# Main.net
KiCad netlist of a schematic drawn in Altium Designer
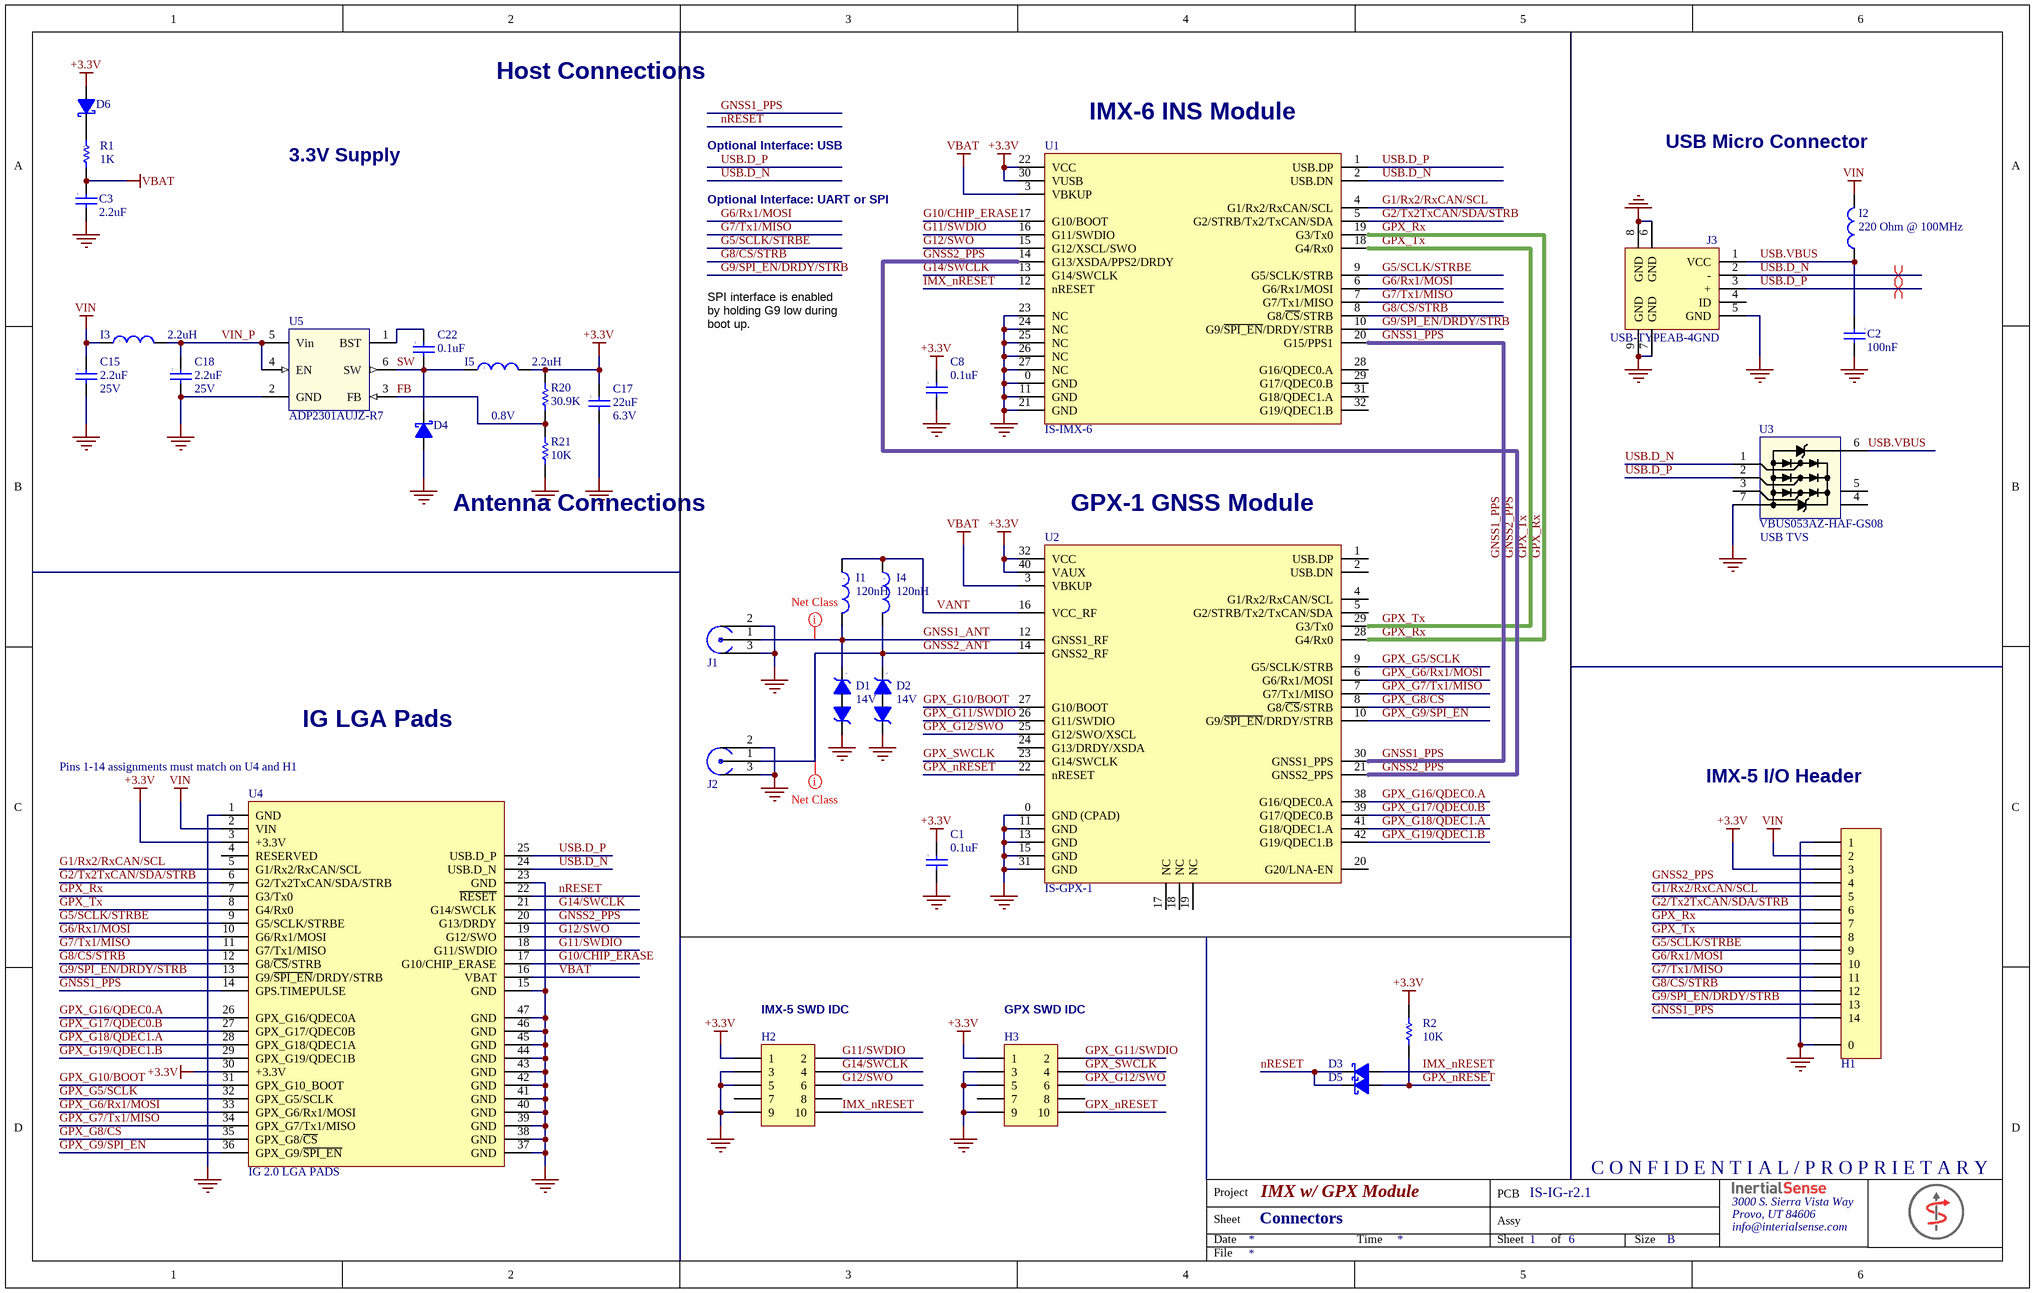
[diagram p0: Main.SchDoc]

(export (version "E")
  (design (tool "Eeschema 10.0.6"))
  (components
    (comp (ref "C1")
      (value "0.1uF")
      (footprint "0402")
      (description "CAP CER .10UF 50V X7R 10% 0402")
      (fields
        (field (name "MANUFACTURER") "TDK Corporation")
        (field (name "MANUFACTURER PART NUMBER") "C1005X7R1H104K")
        (field (name "PUBLISHER") "Altium Limited")
      )
      (libsource (lib "General") (part "Cap"))
    )
    (comp (ref "C2")
      (value "100nF")
      (footprint "0402")
      (description "CAP CER .10UF 50V X7R 10% 0402")
      (fields
        (field (name "MANUFACTURER") "TDK Corporation")
        (field (name "MANUFACTURER PART NUMBER") "C1005X7R1H104K")
        (field (name "PUBLISHER") "Altium Limited")
      )
      (libsource (lib "General") (part "Cap"))
    )
    (comp (ref "C3")
      (value "2.2uF")
      (footprint "0402")
      (description "0402 2.2 uF 6.3 V ±10% Tolerance X6S Multilayer Ceramic Capacitor")
      (fields
        (field (name "MANUFACTURER") "Murata")
        (field (name "MANUFACTURER PART NUMBER") "GRM155C80J225KE95D")
        (field (name "PUBLISHER") "Altium Limited")
      )
      (libsource (lib "General") (part "Cap"))
    )
    (comp (ref "C8")
      (value "0.1uF")
      (footprint "0402")
      (description "CAP CER .10UF 50V X7R 10% 0402")
      (fields
        (field (name "MANUFACTURER") "TDK Corporation")
        (field (name "MANUFACTURER PART NUMBER") "C1005X7R1H104K")
        (field (name "PUBLISHER") "Altium Limited")
      )
      (libsource (lib "General") (part "Cap"))
    )
    (comp (ref "C15")
      (value "2.2uF")
      (footprint "0603")
      (description "CAP CER 2.2UF 25V X6S 0603")
      (fields
        (field (name "MANUFACTURER") "Murata")
        (field (name "MANUFACTURER PART NUMBER") "GRT188C81E225KE13D")
        (field (name "VOLTAGE RATING") "25V")
        (field (name "PUBLISHER") "Altium Limited")
      )
      (libsource (lib "General") (part "Cap"))
    )
    (comp (ref "C17")
      (value "22uF")
      (footprint "0603")
      (description "CAP CER 22UF 6.3V X6S 0603")
      (fields
        (field (name "MANUFACTURER") "Murata")
        (field (name "MANUFACTURER PART NUMBER") "GRM188C80J226ME15D")
        (field (name "VOLTAGE RATING") "6.3V")
        (field (name "PUBLISHER") "Altium Limited")
      )
      (libsource (lib "General") (part "Cap"))
    )
    (comp (ref "C18")
      (value "2.2uF")
      (footprint "0603")
      (description "CAP CER 2.2UF 25V X6S 0603")
      (fields
        (field (name "MANUFACTURER") "Murata")
        (field (name "MANUFACTURER PART NUMBER") "GRT188C81E225KE13D")
        (field (name "VOLTAGE RATING") "25V")
        (field (name "PUBLISHER") "Altium Limited")
      )
      (libsource (lib "General") (part "Cap"))
    )
    (comp (ref "C22")
      (value "0.1uF")
      (footprint "0402")
      (description "CAP CER 0.1UF 50V X7R 0402")
      (fields
        (field (name "MANUFACTURER") "TDK")
        (field (name "MANUFACTURER PART NUMBER") "CGA2B3X7R1H104K050BB")
        (field (name "PUBLISHER") "Altium Limited")
      )
      (libsource (lib "General") (part "Cap"))
    )
    (comp (ref "D1")
      (value "Diode - Bidirectional Zener")
      (footprint "R0402")
      (description "LITTELFUSE - PESD0402-140 - DIODE, ESD PROTECTION, 0402, FULL REEL")
      (fields
        (field (name "MANUFACTURER") "Littelfuse")
        (field (name "MANUFACTURER PART NUMBER") "PESD0402-140")
        (field (name "WORKING VOLTAGE") "14V")
      )
      (libsource (lib "General") (part "Diode - Bidirectional Zener"))
    )
    (comp (ref "D2")
      (value "Diode - Bidirectional Zener")
      (footprint "R0402")
      (description "LITTELFUSE - PESD0402-140 - DIODE, ESD PROTECTION, 0402, FULL REEL")
      (fields
        (field (name "MANUFACTURER") "Littelfuse")
        (field (name "MANUFACTURER PART NUMBER") "PESD0402-140")
        (field (name "WORKING VOLTAGE") "14V")
      )
      (libsource (lib "General") (part "Diode - Bidirectional Zener"))
    )
    (comp (ref "D3")
      (value "Diode - Schottky")
      (footprint "D0402")
      (description "CDBQR0130L; SMT Schottky Diode; 35V 100mA; 2-Pin SOD-923F (0402)")
      (fields (field (name "MANUFACTURER") "Comchip") (field (name "MANUFACTURER PART NUMBER") "CDBQR0130L"))
      (libsource (lib "General") (part "Diode - Schottky"))
    )
    (comp (ref "D4")
      (value "Diode - Schottky")
      (footprint "D0603B")
      (description "DIODE SCHOTTKY 30V 2A 0603")
      (fields
        (field (name "MANUFACTURER") "Vishay")
        (field (name "MANUFACTURER PART NUMBER") "VSKY20301608-G4-08")
      )
      (libsource (lib "General") (part "Diode - Schottky"))
    )
    (comp (ref "D5")
      (value "Diode - Schottky")
      (footprint "D0402")
      (description "CDBQR0130L; SMT Schottky Diode; 35V 100mA; 2-Pin SOD-923F (0402)")
      (fields (field (name "MANUFACTURER") "Comchip") (field (name "MANUFACTURER PART NUMBER") "CDBQR0130L"))
      (libsource (lib "General") (part "Diode - Schottky"))
    )
    (comp (ref "D6")
      (value "Diode - Schottky")
      (footprint "D0603B")
      (description "DIODE SCHOTTKY 30V 2A 0603")
      (fields
        (field (name "MANUFACTURER") "Vishay")
        (field (name "MANUFACTURER PART NUMBER") "VSKY20301608-G4-08")
      )
      (libsource (lib "General") (part "Diode - Schottky"))
    )
    (comp (ref "H1")
      (value "Hdr - 14pin - mount")
      (footprint "SM14B-GHS-TB(LF)(SN)")
      (description "Conn Shrouded Header HDR 14 POS 1.25mm Solder ST Top Entry SMD T/R")
      (fields
        (field (name "MANUFACTURER") "JST")
        (field (name "MANUFACTURER PART NUMBER") "SM14B-GHS-TB(LF)(SN)")
      )
      (libsource (lib "Connectors") (part "Hdr - 14pin - mount"))
    )
    (comp (ref "H2")
      (value "Hdr - 5x2pin")
      (footprint "FTSH-105-01-L-DV-K-A-P")
      (description "CONN HEADER 10POS DUAL .05\" SMD")
      (fields
        (field (name "MANUFACTURER") "Samtec")
        (field (name "MANUFACTURER PART NUMBER") "FTSH-105-01-L-DV-K-A-P")
      )
      (libsource (lib "Connectors") (part "Hdr - 5x2pin"))
    )
    (comp (ref "H3")
      (value "Hdr - 5x2pin")
      (footprint "FTSH-105-01-L-DV-K-A-P")
      (description "CONN HEADER 10POS DUAL .05\" SMD")
      (fields
        (field (name "MANUFACTURER") "Samtec")
        (field (name "MANUFACTURER PART NUMBER") "FTSH-105-01-L-DV-K-A-P")
      )
      (libsource (lib "Connectors") (part "Hdr - 5x2pin"))
    )
    (comp (ref "I1")
      (value "120nH")
      (footprint "0402")
      (description "Inductor RF Chip Wirewound 120nH 5% 100MHz 20Q-Factor 110mA 2.66Ohm DCR 0402 Paper T/R")
      (fields
        (field (name "MANUFACTURER") "Murata")
        (field (name "MANUFACTURER PART NUMBER") "LQW15ANR12J00D")
      )
      (libsource (lib "General") (part "Inductor"))
    )
    (comp (ref "I2")
      (value "220 Ohm @ 100MHz")
      (footprint "I0603")
      (description "FERRITE CHIP 220 OHM 2500MA 0603")
      (fields
        (field (name "MANUFACTURER") "Murata Electronics North America")
        (field (name "MANUFACTURER PART NUMBER") "BLM18SG221TN1D")
      )
      (libsource (lib "") (part "Inductor_1"))
    )
    (comp (ref "I3")
      (value "2.2uH")
      (footprint "0806")
      (description "FIXED IND 2.2UH 1.2A 110 MOHM")
      (fields
        (field (name "MANUFACTURER") "TDK")
        (field (name "MANUFACTURER PART NUMBER") "MLP2016H2R2MT0S1")
      )
      (libsource (lib "General") (part "Inductor"))
    )
    (comp (ref "I4")
      (value "120nH")
      (footprint "0402")
      (description "Inductor RF Chip Wirewound 120nH 5% 100MHz 20Q-Factor 110mA 2.66Ohm DCR 0402 Paper T/R")
      (fields
        (field (name "MANUFACTURER") "Murata")
        (field (name "MANUFACTURER PART NUMBER") "LQW15ANR12J00D")
      )
      (libsource (lib "General") (part "Inductor"))
    )
    (comp (ref "I5")
      (value "2.2uH")
      (footprint "0806")
      (description "FIXED IND 2.2UH 1.2A 110 MOHM")
      (fields
        (field (name "MANUFACTURER") "TDK")
        (field (name "MANUFACTURER PART NUMBER") "MLP2016H2R2MT0S1")
      )
      (libsource (lib "General") (part "Inductor"))
    )
    (comp (ref "J1")
      (value "RF - GND x 2")
      (footprint "RF UMC SMD")
      (description "CONN UMC RCPT STR 50 OHM SMD")
      (fields
        (field (name "MANUFACTURER") "Emerson Network Power Connectivity Johnson")
        (field (name "MANUFACTURER PART NUMBER") "128-0711-201")
      )
      (libsource (lib "Connectors") (part "RF - GND x 2"))
    )
    (comp (ref "J2")
      (value "RF - GND x 2")
      (footprint "RF UMC SMD")
      (description "CONN UMC RCPT STR 50 OHM SMD")
      (fields
        (field (name "MANUFACTURER") "Emerson Network Power Connectivity Johnson")
        (field (name "MANUFACTURER PART NUMBER") "128-0711-201")
      )
      (libsource (lib "Connectors") (part "RF - GND x 2"))
    )
    (comp (ref "J3")
      (value "USB-TYPEAB-4GND")
      (footprint "USB Micro AB R/A THR")
      (description "CONN USB AB 4POS")
      (fields
        (field (name "MANUFACTURER") "Amphenol FCI")
        (field (name "MANUFACTURER PART NUMBER") "10118194-0001LF")
      )
      (libsource (lib "Connectors") (part "USB-TYPEAB-4GND"))
    )
    (comp (ref "R1")
      (value "1K")
      (footprint "R0402")
      (description "1 kOhms ±1% 0.063W, 1/16W Chip Resistor 0402 (1005 Metric) Moisture Resistant Thick Film")
      (fields
        (field (name "MANUFACTURER") "Yageo")
        (field (name "MANUFACTURER PART NUMBER") "RC0402FR-071KL")
      )
      (libsource (lib "General") (part "Res"))
    )
    (comp (ref "R2")
      (value "10K")
      (footprint "R0402")
      (description "10 kOhms 1% 0.063W, 1/16W Chip Resistor 0402 (1005 Metric) Moisture Resistant Thick Film")
      (fields
        (field (name "MANUFACTURER") "Stackpole Electronics")
        (field (name "MANUFACTURER PART NUMBER") "RMCF0402FT10K0")
      )
      (libsource (lib "General") (part "Res"))
    )
    (comp (ref "R20")
      (value "30.9K")
      (footprint "R0402")
      (description "RES TF 30.9K OHM 1% 1/16W 0402")
      (fields
        (field (name "MANUFACTURER") "Stackpole Electronics Inc")
        (field (name "MANUFACTURER PART NUMBER") "RMCF0402FT30K9")
      )
      (libsource (lib "General") (part "Res"))
    )
    (comp (ref "R21")
      (value "10K")
      (footprint "R0402")
      (description "RES 10.0K OHM 1/16W 1% 0402 SMD")
      (fields
        (field (name "MANUFACTURER") "Yageo")
        (field (name "MANUFACTURER PART NUMBER") "RC0402FR-0710KL")
      )
      (libsource (lib "General") (part "Res"))
    )
    (comp (ref "U1")
      (value "IMX")
      (footprint "IS-IMX-6")
      (description "Inertial Sense IMX")
      (fields
        (field (name "MANUFACTURER") "Inertial Sense")
        (field (name "MANUFACTURER PART NUMBER") "IS-IMX-6")
      )
      (libsource (lib "IS-IMX-6") (part "IS-IMX-6"))
    )
    (comp (ref "U2")
      (value "GPX")
      (footprint "IS-GPX-1.0")
      (description "Inertial Sense GPX")
      (fields
        (field (name "MANUFACTURER") "Inertial Sense")
        (field (name "MANUFACTURER PART NUMBER") "IS-GPX-1")
      )
      (libsource (lib "IS-GPX-1") (part "IS-GPX-1.0"))
    )
    (comp (ref "U3")
      (value "VBUS053")
      (footprint "QFN50P160X160X60-6N")
      (description "ESD SUPPRESS 5.5V 36W 3-Line USB")
      (fields
        (field (name "MANUFACTURER") "Vishay Semiconductors")
        (field (name "MANUFACTURER PART NUMBER") "VBUS053AZ-HAF-GS08")
      )
      (libsource (lib "ICs") (part "VBUS053"))
    )
    (comp (ref "U4")
      (value "IG 2.0 LGA PADS")
      (footprint "IG-2.0_LGA")
      (description "IMX multi-frequency RTK-GNSS Module")
      (libsource (lib "Sensors") (part "IG_2.0_LGA"))
    )
    (comp (ref "U5")
      (value "ADP2301")
      (footprint "MO-178-AB")
      (description "IC BUCK ADJ 1.2A 6TSOT")
      (fields
        (field (name "MANUFACTURER") "Analog Devices Inc")
        (field (name "MANUFACTURER PART NUMBER") "ADP2301AUJZ-R7")
      )
      (libsource (lib "ICs") (part "ADP2301"))
    )
  )
  (nets
    (net (code "1") (name "+3.3V") (class "Default")
      (node (ref "C1") (pin "1") (pinfunction "1_1") (pintype "passive"))
      (node (ref "C17") (pin "1") (pinfunction "1_1") (pintype "passive"))
      (node (ref "C8") (pin "1") (pinfunction "1_1") (pintype "passive"))
      (node (ref "D6") (pin "A") (pinfunction "A_A") (pintype "passive"))
      (node (ref "H1") (pin "3") (pinfunction "3_3") (pintype "passive"))
      (node (ref "H2") (pin "1") (pinfunction "1_1") (pintype "passive"))
      (node (ref "H3") (pin "1") (pinfunction "1_1") (pintype "passive"))
      (node (ref "I5") (pin "2") (pinfunction "2_2") (pintype "passive"))
      (node (ref "R2") (pin "1") (pinfunction "1_1") (pintype "passive"))
      (node (ref "R20") (pin "2") (pinfunction "2_2") (pintype "passive"))
      (node (ref "U1") (pin "22") (pinfunction "VCC_22") (pintype "power_in"))
      (node (ref "U1") (pin "30") (pinfunction "VUSB_30") (pintype "power_in"))
      (node (ref "U2") (pin "32") (pinfunction "VCC_32") (pintype "power_in"))
      (node (ref "U2") (pin "40") (pinfunction "VAUX_40") (pintype "power_in"))
      (node (ref "U4") (pin "3") (pinfunction "+3.3V_3") (pintype "passive"))
      (node (ref "U4") (pin "30") (pinfunction "+3.3V_30") (pintype "passive"))
    )
    (net (code "2") (name "/FB") (class "Default")
      (node (ref "R20") (pin "1") (pinfunction "1_1") (pintype "passive"))
      (node (ref "R21") (pin "2") (pinfunction "2_2") (pintype "passive"))
      (node (ref "U5") (pin "3") (pinfunction "FB_3") (pintype "input"))
    )
    (net (code "3") (name "/G1{slash}Rx2{slash}RxCAN{slash}SCL") (class "Default")
      (node (ref "H1") (pin "5") (pinfunction "5_5") (pintype "passive"))
      (node (ref "U1") (pin "4") (pinfunction "G1/Rx2/RxCAN/SCL_4") (pintype "passive"))
      (node (ref "U4") (pin "5") (pinfunction "G1/Rx2/RxCAN/SCL_5") (pintype "passive"))
    )
    (net (code "4") (name "/G2{slash}Tx2TxCAN{slash}SDA{slash}STRB") (class "Default")
      (node (ref "H1") (pin "6") (pinfunction "6_6") (pintype "passive"))
      (node (ref "U1") (pin "5") (pinfunction "G2/STRB/Tx2/TxCAN/SDA_5") (pintype "passive"))
      (node (ref "U4") (pin "6") (pinfunction "G2/Tx2TxCAN/SDA/STRB_6") (pintype "passive"))
    )
    (net (code "5") (name "/G5{slash}SCLK{slash}STRBE") (class "Default")
      (node (ref "H1") (pin "9") (pinfunction "9_9") (pintype "passive"))
      (node (ref "U1") (pin "9") (pinfunction "G5/SCLK/STRB_9") (pintype "passive"))
      (node (ref "U4") (pin "9") (pinfunction "G5/SCLK/STRBE_9") (pintype "passive"))
    )
    (net (code "6") (name "/G6{slash}Rx1{slash}MOSI") (class "Default")
      (node (ref "H1") (pin "10") (pinfunction "10_10") (pintype "passive"))
      (node (ref "U1") (pin "6") (pinfunction "G6/Rx1/MOSI_6") (pintype "passive"))
      (node (ref "U4") (pin "10") (pinfunction "G6/Rx1/MOSI_10") (pintype "passive"))
    )
    (net (code "7") (name "/G7{slash}Tx1{slash}MISO") (class "Default")
      (node (ref "H1") (pin "11") (pinfunction "11_11") (pintype "passive"))
      (node (ref "U1") (pin "7") (pinfunction "G7/Tx1/MISO_7") (pintype "passive"))
      (node (ref "U4") (pin "11") (pinfunction "G7/Tx1/MISO_11") (pintype "passive"))
    )
    (net (code "8") (name "/G8{slash}~{CS}{slash}STRB") (class "Default")
      (node (ref "H1") (pin "12") (pinfunction "12_12") (pintype "passive"))
      (node (ref "U1") (pin "8") (pinfunction "G8/~{CS}/STRB_8") (pintype "passive"))
      (node (ref "U4") (pin "12") (pinfunction "G8/~{CS}/STRB_12") (pintype "passive"))
    )
    (net (code "9") (name "/G9{slash}~{SPI_EN}{slash}DRDY{slash}STRB") (class "Default")
      (node (ref "H1") (pin "13") (pinfunction "13_13") (pintype "passive"))
      (node (ref "U1") (pin "10") (pinfunction "G9/~{SPI_EN}/DRDY/STRB_10") (pintype "passive"))
      (node (ref "U4") (pin "13") (pinfunction "G9/~{SPI_EN}/DRDY/STRB_13") (pintype "passive"))
    )
    (net (code "10") (name "/G10{slash}CHIP_ERASE") (class "Default")
      (node (ref "U1") (pin "17") (pinfunction "G10/BOOT_17") (pintype "passive"))
      (node (ref "U4") (pin "17") (pinfunction "G10/CHIP_ERASE_17") (pintype "passive"))
    )
    (net (code "11") (name "/G11{slash}SWDIO") (class "Default")
      (node (ref "H2") (pin "2") (pinfunction "2_2") (pintype "passive"))
      (node (ref "U1") (pin "16") (pinfunction "G11/SWDIO_16") (pintype "passive"))
      (node (ref "U4") (pin "18") (pinfunction "G11/SWDIO_18") (pintype "passive"))
    )
    (net (code "12") (name "/G12{slash}SWO") (class "Default")
      (node (ref "H2") (pin "6") (pinfunction "6_6") (pintype "passive"))
      (node (ref "U1") (pin "15") (pinfunction "G12/XSCL/SWO_15") (pintype "passive"))
      (node (ref "U4") (pin "19") (pinfunction "G12/SWO_19") (pintype "passive"))
    )
    (net (code "13") (name "/G14{slash}SWCLK") (class "Default")
      (node (ref "H2") (pin "4") (pinfunction "4_4") (pintype "passive"))
      (node (ref "U1") (pin "13") (pinfunction "G14/SWCLK_13") (pintype "passive"))
      (node (ref "U4") (pin "21") (pinfunction "G14/SWCLK_21") (pintype "passive"))
    )
    (net (code "14") (name "/GNSS1_ANT") (class "Default")
      (node (ref "D1") (pin "1") (pinfunction "1_1") (pintype "passive"))
      (node (ref "I1") (pin "2") (pinfunction "2_2") (pintype "passive"))
      (node (ref "J1") (pin "1") (pinfunction "1_1") (pintype "passive"))
      (node (ref "U2") (pin "12") (pinfunction "GNSS1_RF_12") (pintype "passive"))
    )
    (net (code "15") (name "/GNSS1_PPS") (class "Default")
      (node (ref "H1") (pin "14") (pinfunction "14_14") (pintype "passive"))
      (node (ref "U1") (pin "20") (pinfunction "G15/PPS1_20") (pintype "passive"))
      (node (ref "U2") (pin "30") (pinfunction "GNSS1_PPS_30") (pintype "passive"))
      (node (ref "U4") (pin "14") (pinfunction "GPS.TIMEPULSE_14") (pintype "passive"))
    )
    (net (code "16") (name "/GNSS2_ANT") (class "Default")
      (node (ref "D2") (pin "1") (pinfunction "1_1") (pintype "passive"))
      (node (ref "I4") (pin "2") (pinfunction "2_2") (pintype "passive"))
      (node (ref "J2") (pin "1") (pinfunction "1_1") (pintype "passive"))
      (node (ref "U2") (pin "14") (pinfunction "GNSS2_RF_14") (pintype "passive"))
    )
    (net (code "17") (name "/GNSS2_PPS") (class "Default")
      (node (ref "H1") (pin "4") (pinfunction "4_4") (pintype "passive"))
      (node (ref "U1") (pin "14") (pinfunction "G13/XSDA/PPS2/DRDY_14") (pintype "passive"))
      (node (ref "U2") (pin "21") (pinfunction "GNSS2_PPS_21") (pintype "passive"))
      (node (ref "U4") (pin "20") (pinfunction "G13/DRDY_20") (pintype "passive"))
    )
    (net (code "18") (name "/GPX_G5{slash}SCLK") (class "Default")
      (node (ref "U2") (pin "9") (pinfunction "G5/SCLK/STRB_9") (pintype "passive"))
      (node (ref "U4") (pin "32") (pinfunction "GPX_G5/SCLK_32") (pintype "passive"))
    )
    (net (code "19") (name "/GPX_G6{slash}Rx1{slash}MOSI") (class "Default")
      (node (ref "U2") (pin "6") (pinfunction "G6/Rx1/MOSI_6") (pintype "passive"))
      (node (ref "U4") (pin "33") (pinfunction "GPX_G6/Rx1/MOSI_33") (pintype "passive"))
    )
    (net (code "20") (name "/GPX_G7{slash}Tx1{slash}MISO") (class "Default")
      (node (ref "U2") (pin "7") (pinfunction "G7/Tx1/MISO_7") (pintype "passive"))
      (node (ref "U4") (pin "34") (pinfunction "GPX_G7/Tx1/MISO_34") (pintype "passive"))
    )
    (net (code "21") (name "/GPX_G8{slash}~{CS}") (class "Default")
      (node (ref "U2") (pin "8") (pinfunction "G8/~{CS}/STRB_8") (pintype "passive"))
      (node (ref "U4") (pin "35") (pinfunction "GPX_G8/~{CS}_35") (pintype "passive"))
    )
    (net (code "22") (name "/GPX_G9{slash}~{SPI_EN}") (class "Default")
      (node (ref "U2") (pin "10") (pinfunction "G9/~{SPI_EN}/DRDY/STRB_10") (pintype "passive"))
      (node (ref "U4") (pin "36") (pinfunction "GPX_G9/~{SPI_EN}_36") (pintype "passive"))
    )
    (net (code "23") (name "/GPX_G10{slash}BOOT") (class "Default")
      (node (ref "U2") (pin "27") (pinfunction "G10/BOOT_27") (pintype "passive"))
      (node (ref "U4") (pin "31") (pinfunction "GPX_G10_BOOT_31") (pintype "passive"))
    )
    (net (code "24") (name "/GPX_G11{slash}SWDIO") (class "Default")
      (node (ref "H3") (pin "2") (pinfunction "2_2") (pintype "passive"))
      (node (ref "U2") (pin "26") (pinfunction "G11/SWDIO_26") (pintype "passive"))
    )
    (net (code "25") (name "/GPX_G12{slash}SWO") (class "Default")
      (node (ref "H3") (pin "6") (pinfunction "6_6") (pintype "passive"))
      (node (ref "U2") (pin "25") (pinfunction "G12/SWO/XSCL_25") (pintype "passive"))
    )
    (net (code "26") (name "/GPX_G16{slash}QDEC0.A") (class "Default")
      (node (ref "U2") (pin "38") (pinfunction "G16/QDEC0.A_38") (pintype "passive"))
      (node (ref "U4") (pin "26") (pinfunction "GPX_G16/QDEC0A_26") (pintype "passive"))
    )
    (net (code "27") (name "/GPX_G17{slash}QDEC0.B") (class "Default")
      (node (ref "U2") (pin "39") (pinfunction "G17/QDEC0.B_39") (pintype "passive"))
      (node (ref "U4") (pin "27") (pinfunction "GPX_G17/QDEC0B_27") (pintype "passive"))
    )
    (net (code "28") (name "/GPX_G18{slash}QDEC1.A") (class "Default")
      (node (ref "U2") (pin "41") (pinfunction "G18/QDEC1.A_41") (pintype "passive"))
      (node (ref "U4") (pin "28") (pinfunction "GPX_G18/QDEC1A_28") (pintype "passive"))
    )
    (net (code "29") (name "/GPX_G19{slash}QDEC1.B") (class "Default")
      (node (ref "U2") (pin "42") (pinfunction "G19/QDEC1.B_42") (pintype "passive"))
      (node (ref "U4") (pin "29") (pinfunction "GPX_G19/QDEC1B_29") (pintype "passive"))
    )
    (net (code "30") (name "/GPX_Rx") (class "Default")
      (node (ref "H1") (pin "7") (pinfunction "7_7") (pintype "passive"))
      (node (ref "U1") (pin "19") (pinfunction "G3/Tx0_19") (pintype "passive"))
      (node (ref "U2") (pin "28") (pinfunction "G4/Rx0_28") (pintype "passive"))
      (node (ref "U4") (pin "7") (pinfunction "G3/Tx0_7") (pintype "passive"))
    )
    (net (code "31") (name "/GPX_SWCLK") (class "Default")
      (node (ref "H3") (pin "4") (pinfunction "4_4") (pintype "passive"))
      (node (ref "U2") (pin "23") (pinfunction "G14/SWCLK_23") (pintype "passive"))
    )
    (net (code "32") (name "/GPX_Tx") (class "Default")
      (node (ref "H1") (pin "8") (pinfunction "8_8") (pintype "passive"))
      (node (ref "U1") (pin "18") (pinfunction "G4/Rx0_18") (pintype "passive"))
      (node (ref "U2") (pin "29") (pinfunction "G3/Tx0_29") (pintype "passive"))
      (node (ref "U4") (pin "8") (pinfunction "G4/Rx0_8") (pintype "passive"))
    )
    (net (code "33") (name "/GPX_nRESET") (class "Default")
      (node (ref "D5") (pin "A") (pinfunction "A_A") (pintype "passive"))
      (node (ref "H3") (pin "10") (pinfunction "10_10") (pintype "passive"))
      (node (ref "R2") (pin "2") (pinfunction "2_2") (pintype "passive"))
      (node (ref "U2") (pin "22") (pinfunction "nRESET_22") (pintype "passive"))
    )
    (net (code "34") (name "/IMX_nRESET") (class "Default")
      (node (ref "D3") (pin "A") (pinfunction "A_A") (pintype "passive"))
      (node (ref "H2") (pin "10") (pinfunction "10_10") (pintype "passive"))
      (node (ref "U1") (pin "12") (pinfunction "nRESET_12") (pintype "passive"))
    )
    (net (code "35") (name "/SW") (class "Default")
      (node (ref "C22") (pin "2") (pinfunction "2_2") (pintype "passive"))
      (node (ref "D4") (pin "C") (pinfunction "C_C") (pintype "passive"))
      (node (ref "I5") (pin "1") (pinfunction "1_1") (pintype "passive"))
      (node (ref "U5") (pin "6") (pinfunction "SW_6") (pintype "output"))
    )
    (net (code "36") (name "/USB.D_N") (class "Default")
      (node (ref "J3") (pin "2") (pinfunction "-_2") (pintype "passive"))
      (node (ref "U1") (pin "2") (pinfunction "USB.DN_2") (pintype "passive"))
      (node (ref "U3") (pin "1") (pintype "passive"))
      (node (ref "U4") (pin "24") (pinfunction "USB.D_N_24") (pintype "passive"))
    )
    (net (code "37") (name "/USB.D_P") (class "Default")
      (node (ref "J3") (pin "3") (pinfunction "+_3") (pintype "passive"))
      (node (ref "U1") (pin "1") (pinfunction "USB.DP_1") (pintype "passive"))
      (node (ref "U3") (pin "2") (pintype "passive"))
      (node (ref "U4") (pin "25") (pinfunction "USB.D_P_25") (pintype "passive"))
    )
    (net (code "38") (name "/USB.VBUS") (class "Default")
      (node (ref "C2") (pin "1") (pinfunction "1_1") (pintype "passive"))
      (node (ref "I2") (pin "2") (pinfunction "2_2") (pintype "passive"))
      (node (ref "J3") (pin "1") (pinfunction "VCC_1") (pintype "passive"))
      (node (ref "U3") (pin "6") (pintype "passive"))
    )
    (net (code "39") (name "/VANT") (class "Default")
      (node (ref "I1") (pin "1") (pinfunction "1_1") (pintype "passive"))
      (node (ref "I4") (pin "1") (pinfunction "1_1") (pintype "passive"))
      (node (ref "U2") (pin "16") (pinfunction "VCC_RF_16") (pintype "power_in"))
    )
    (net (code "40") (name "/VIN_P") (class "Default")
      (node (ref "C18") (pin "1") (pinfunction "1_1") (pintype "passive"))
      (node (ref "I3") (pin "2") (pinfunction "2_2") (pintype "passive"))
      (node (ref "U5") (pin "4") (pinfunction "EN_4") (pintype "input"))
      (node (ref "U5") (pin "5") (pinfunction "Vin_5") (pintype "power_in"))
    )
    (net (code "41") (name "/nRESET") (class "Default")
      (node (ref "D3") (pin "C") (pinfunction "C_C") (pintype "passive"))
      (node (ref "D5") (pin "C") (pinfunction "C_C") (pintype "passive"))
      (node (ref "U4") (pin "22") (pinfunction "~{RESET}_22") (pintype "passive"))
    )
    (net (code "42") (name "GND") (class "Default")
      (node (ref "C1") (pin "2") (pinfunction "2_2") (pintype "passive"))
      (node (ref "C15") (pin "2") (pinfunction "2_2") (pintype "passive"))
      (node (ref "C17") (pin "2") (pinfunction "2_2") (pintype "passive"))
      (node (ref "C18") (pin "2") (pinfunction "2_2") (pintype "passive"))
      (node (ref "C2") (pin "2") (pinfunction "2_2") (pintype "passive"))
      (node (ref "C3") (pin "2") (pinfunction "2_2") (pintype "passive"))
      (node (ref "C8") (pin "2") (pinfunction "2_2") (pintype "passive"))
      (node (ref "D1") (pin "2") (pinfunction "2_2") (pintype "passive"))
      (node (ref "D2") (pin "2") (pinfunction "2_2") (pintype "passive"))
      (node (ref "D4") (pin "A") (pinfunction "A_A") (pintype "passive"))
      (node (ref "H1") (pin "0") (pinfunction "0_0") (pintype "passive"))
      (node (ref "H1") (pin "1") (pinfunction "1_1") (pintype "passive"))
      (node (ref "H2") (pin "3") (pinfunction "3_3") (pintype "passive"))
      (node (ref "H2") (pin "5") (pinfunction "5_5") (pintype "passive"))
      (node (ref "H2") (pin "9") (pinfunction "9_9") (pintype "passive"))
      (node (ref "H3") (pin "3") (pinfunction "3_3") (pintype "passive"))
      (node (ref "H3") (pin "5") (pinfunction "5_5") (pintype "passive"))
      (node (ref "H3") (pin "9") (pinfunction "9_9") (pintype "passive"))
      (node (ref "J1") (pin "2") (pinfunction "2_2") (pintype "passive"))
      (node (ref "J1") (pin "3") (pinfunction "3_3") (pintype "passive"))
      (node (ref "J2") (pin "2") (pinfunction "2_2") (pintype "passive"))
      (node (ref "J2") (pin "3") (pinfunction "3_3") (pintype "passive"))
      (node (ref "J3") (pin "5") (pinfunction "GND_5") (pintype "passive"))
      (node (ref "J3") (pin "6") (pinfunction "GND_6") (pintype "passive"))
      (node (ref "J3") (pin "7") (pinfunction "GND_7") (pintype "passive"))
      (node (ref "J3") (pin "8") (pinfunction "GND_8") (pintype "passive"))
      (node (ref "J3") (pin "9") (pinfunction "GND_9") (pintype "passive"))
      (node (ref "R21") (pin "1") (pinfunction "1_1") (pintype "passive"))
      (node (ref "U1") (pin "0") (pinfunction "GND_0") (pintype "power_in"))
      (node (ref "U1") (pin "11") (pinfunction "GND_11") (pintype "power_in"))
      (node (ref "U1") (pin "21") (pinfunction "GND_21") (pintype "power_in"))
      (node (ref "U1") (pin "23") (pinfunction "NC_23") (pintype "power_in"))
      (node (ref "U1") (pin "24") (pinfunction "NC_24") (pintype "power_in"))
      (node (ref "U1") (pin "25") (pinfunction "NC_25") (pintype "power_in"))
      (node (ref "U1") (pin "26") (pinfunction "NC_26") (pintype "power_in"))
      (node (ref "U1") (pin "27") (pinfunction "NC_27") (pintype "power_in"))
      (node (ref "U2") (pin "0") (pinfunction "GND_(CPAD)_0") (pintype "power_in"))
      (node (ref "U2") (pin "11") (pinfunction "GND_11") (pintype "power_in"))
      (node (ref "U2") (pin "13") (pinfunction "GND_13") (pintype "power_in"))
      (node (ref "U2") (pin "15") (pinfunction "GND_15") (pintype "power_in"))
      (node (ref "U2") (pin "31") (pinfunction "GND_31") (pintype "power_in"))
      (node (ref "U3") (pin "7") (pintype "passive"))
      (node (ref "U4") (pin "1") (pinfunction "GND_1") (pintype "passive"))
      (node (ref "U4") (pin "15") (pinfunction "GND_15") (pintype "passive"))
      (node (ref "U4") (pin "23") (pinfunction "GND_23") (pintype "passive"))
      (node (ref "U4") (pin "37") (pinfunction "GND_37") (pintype "passive"))
      (node (ref "U4") (pin "38") (pinfunction "GND_38") (pintype "passive"))
      (node (ref "U4") (pin "39") (pinfunction "GND_39") (pintype "passive"))
      (node (ref "U4") (pin "40") (pinfunction "GND_40") (pintype "passive"))
      (node (ref "U4") (pin "41") (pinfunction "GND_41") (pintype "passive"))
      (node (ref "U4") (pin "42") (pinfunction "GND_42") (pintype "passive"))
      (node (ref "U4") (pin "43") (pinfunction "GND_43") (pintype "passive"))
      (node (ref "U4") (pin "44") (pinfunction "GND_44") (pintype "passive"))
      (node (ref "U4") (pin "45") (pinfunction "GND_45") (pintype "passive"))
      (node (ref "U4") (pin "46") (pinfunction "GND_46") (pintype "passive"))
      (node (ref "U4") (pin "47") (pinfunction "GND_47") (pintype "passive"))
      (node (ref "U5") (pin "2") (pinfunction "GND_2") (pintype "power_in"))
    )
    (net (code "43") (name "Net-(D6-PadC)") (class "Default")
      (node (ref "D6") (pin "C") (pinfunction "C_C") (pintype "passive"))
      (node (ref "R1") (pin "1") (pinfunction "1_1") (pintype "passive"))
    )
    (net (code "44") (name "Net-(U5-BST)") (class "Default")
      (node (ref "C22") (pin "1") (pinfunction "1_1") (pintype "passive"))
      (node (ref "U5") (pin "1") (pinfunction "BST_1") (pintype "passive"))
    )
    (net (code "45") (name "VBAT") (class "Default")
      (node (ref "C3") (pin "1") (pinfunction "1_1") (pintype "passive"))
      (node (ref "R1") (pin "2") (pinfunction "2_2") (pintype "passive"))
      (node (ref "U1") (pin "3") (pinfunction "VBKUP_3") (pintype "passive"))
      (node (ref "U2") (pin "3") (pinfunction "VBKUP_3") (pintype "passive"))
      (node (ref "U4") (pin "16") (pinfunction "VBAT_16") (pintype "passive"))
    )
    (net (code "46") (name "VIN") (class "Default")
      (node (ref "C15") (pin "1") (pinfunction "1_1") (pintype "passive"))
      (node (ref "H1") (pin "2") (pinfunction "2_2") (pintype "passive"))
      (node (ref "I2") (pin "1") (pinfunction "1_1") (pintype "passive"))
      (node (ref "I3") (pin "1") (pinfunction "1_1") (pintype "passive"))
      (node (ref "U4") (pin "2") (pinfunction "VIN_2") (pintype "passive"))
    )
    (net (code "47") (name "unconnected-(H2-Pad7)") (class "Default")
      (node (ref "H2") (pin "7") (pinfunction "7_7") (pintype "passive"))
    )
    (net (code "48") (name "unconnected-(H2-Pad8)") (class "Default")
      (node (ref "H2") (pin "8") (pinfunction "8_8") (pintype "passive"))
    )
    (net (code "49") (name "unconnected-(H3-Pad7)") (class "Default")
      (node (ref "H3") (pin "7") (pinfunction "7_7") (pintype "passive"))
    )
    (net (code "50") (name "unconnected-(H3-Pad8)") (class "Default")
      (node (ref "H3") (pin "8") (pinfunction "8_8") (pintype "passive"))
    )
    (net (code "51") (name "unconnected-(J3-ID-Pad4)") (class "Default")
      (node (ref "J3") (pin "4") (pinfunction "ID_4") (pintype "passive"))
    )
    (net (code "52") (name "unconnected-(U1-G16{slash}QDEC0.A-Pad28)") (class "Default")
      (node (ref "U1") (pin "28") (pinfunction "G16/QDEC0.A_28") (pintype "passive"))
    )
    (net (code "53") (name "unconnected-(U1-G17{slash}QDEC0.B-Pad29)") (class "Default")
      (node (ref "U1") (pin "29") (pinfunction "G17/QDEC0.B_29") (pintype "passive"))
    )
    (net (code "54") (name "unconnected-(U1-G18{slash}QDEC1.A-Pad31)") (class "Default")
      (node (ref "U1") (pin "31") (pinfunction "G18/QDEC1.A_31") (pintype "passive"))
    )
    (net (code "55") (name "unconnected-(U1-G19{slash}QDEC1.B-Pad32)") (class "Default")
      (node (ref "U1") (pin "32") (pinfunction "G19/QDEC1.B_32") (pintype "passive"))
    )
    (net (code "56") (name "unconnected-(U2-G1{slash}Rx2{slash}RxCAN{slash}SCL-Pad4)") (class "Default")
      (node (ref "U2") (pin "4") (pinfunction "G1/Rx2/RxCAN/SCL_4") (pintype "passive"))
    )
    (net (code "57") (name "unconnected-(U2-G2{slash}STRB{slash}Tx2{slash}TxCAN{slash}SDA-Pad5)") (class "Default")
      (node (ref "U2") (pin "5") (pinfunction "G2/STRB/Tx2/TxCAN/SDA_5") (pintype "passive"))
    )
    (net (code "58") (name "unconnected-(U2-G13{slash}DRDY{slash}XSDA-Pad24)") (class "Default")
      (node (ref "U2") (pin "24") (pinfunction "G13/DRDY/XSDA_24") (pintype "passive"))
    )
    (net (code "59") (name "unconnected-(U2-G20{slash}LNA-EN-Pad20)") (class "Default")
      (node (ref "U2") (pin "20") (pinfunction "G20/LNA-EN_20") (pintype "passive"))
    )
    (net (code "60") (name "unconnected-(U2-NC-Pad17)") (class "Default")
      (node (ref "U2") (pin "17") (pinfunction "NC_17") (pintype "passive"))
    )
    (net (code "61") (name "unconnected-(U2-NC-Pad18)") (class "Default")
      (node (ref "U2") (pin "18") (pinfunction "NC_18") (pintype "passive"))
    )
    (net (code "62") (name "unconnected-(U2-NC-Pad19)") (class "Default")
      (node (ref "U2") (pin "19") (pinfunction "NC_19") (pintype "passive"))
    )
    (net (code "63") (name "unconnected-(U2-USB.DN-Pad2)") (class "Default")
      (node (ref "U2") (pin "2") (pinfunction "USB.DN_2") (pintype "passive"))
    )
    (net (code "64") (name "unconnected-(U2-USB.DP-Pad1)") (class "Default")
      (node (ref "U2") (pin "1") (pinfunction "USB.DP_1") (pintype "passive"))
    )
    (net (code "65") (name "unconnected-(U3-Pad3)") (class "Default")
      (node (ref "U3") (pin "3") (pintype "passive"))
    )
    (net (code "66") (name "unconnected-(U3-nc-Pad4)") (class "Default")
      (node (ref "U3") (pin "4") (pinfunction "nc_4") (pintype "passive"))
    )
    (net (code "67") (name "unconnected-(U3-nc-Pad5)") (class "Default")
      (node (ref "U3") (pin "5") (pinfunction "nc_5") (pintype "passive"))
    )
    (net (code "68") (name "unconnected-(U4-RESERVED-Pad4)") (class "Default")
      (node (ref "U4") (pin "4") (pinfunction "RESERVED_4") (pintype "passive"))
    )
  )
)
